# Resistors.net
KiCad netlist of a schematic drawn in Altium Designer
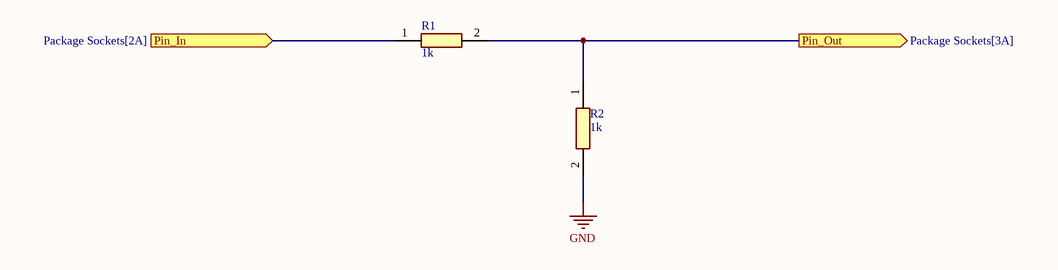
[diagram p0: Resistors.SchDoc]

(export (version "E")
  (design (tool "Eeschema 10.0.6"))
  (components
    (comp (ref "R1")
      (value "1k")
      (footprint "Packaging:RESC1608X55N")
      (description "RMCF0603FT1K00")
      (fields (field (name "MOUSER PART NUMBER") "708-RMCF0603FT1K00"))
      (libsource (lib "") (part "RMCF0603FT1K00_1"))
    )
    (comp (ref "R2")
      (value "1k")
      (footprint "Packaging:RESC1608X55N")
      (description "RMCF0603FT1K00")
      (fields (field (name "MOUSER PART NUMBER") "708-RMCF0603FT1K00"))
      (libsource (lib "Packaging") (part "RMCF0603FT1K00"))
    )
  )
  (nets
    (net (code "1") (name "/Pin_In") (class "Default")
      (node (ref "R1") (pin "1") (pinfunction "1_1") (pintype "passive"))
    )
    (net (code "2") (name "/Pin_Out") (class "Default")
      (node (ref "R1") (pin "2") (pinfunction "2_2") (pintype "passive"))
      (node (ref "R2") (pin "1") (pinfunction "1_1") (pintype "passive"))
    )
    (net (code "3") (name "GND") (class "Default")
      (node (ref "R2") (pin "2") (pinfunction "2_2") (pintype "passive"))
    )
  )
)
